# Sheet_2.net
KiCad netlist of a schematic drawn in EasyEDA
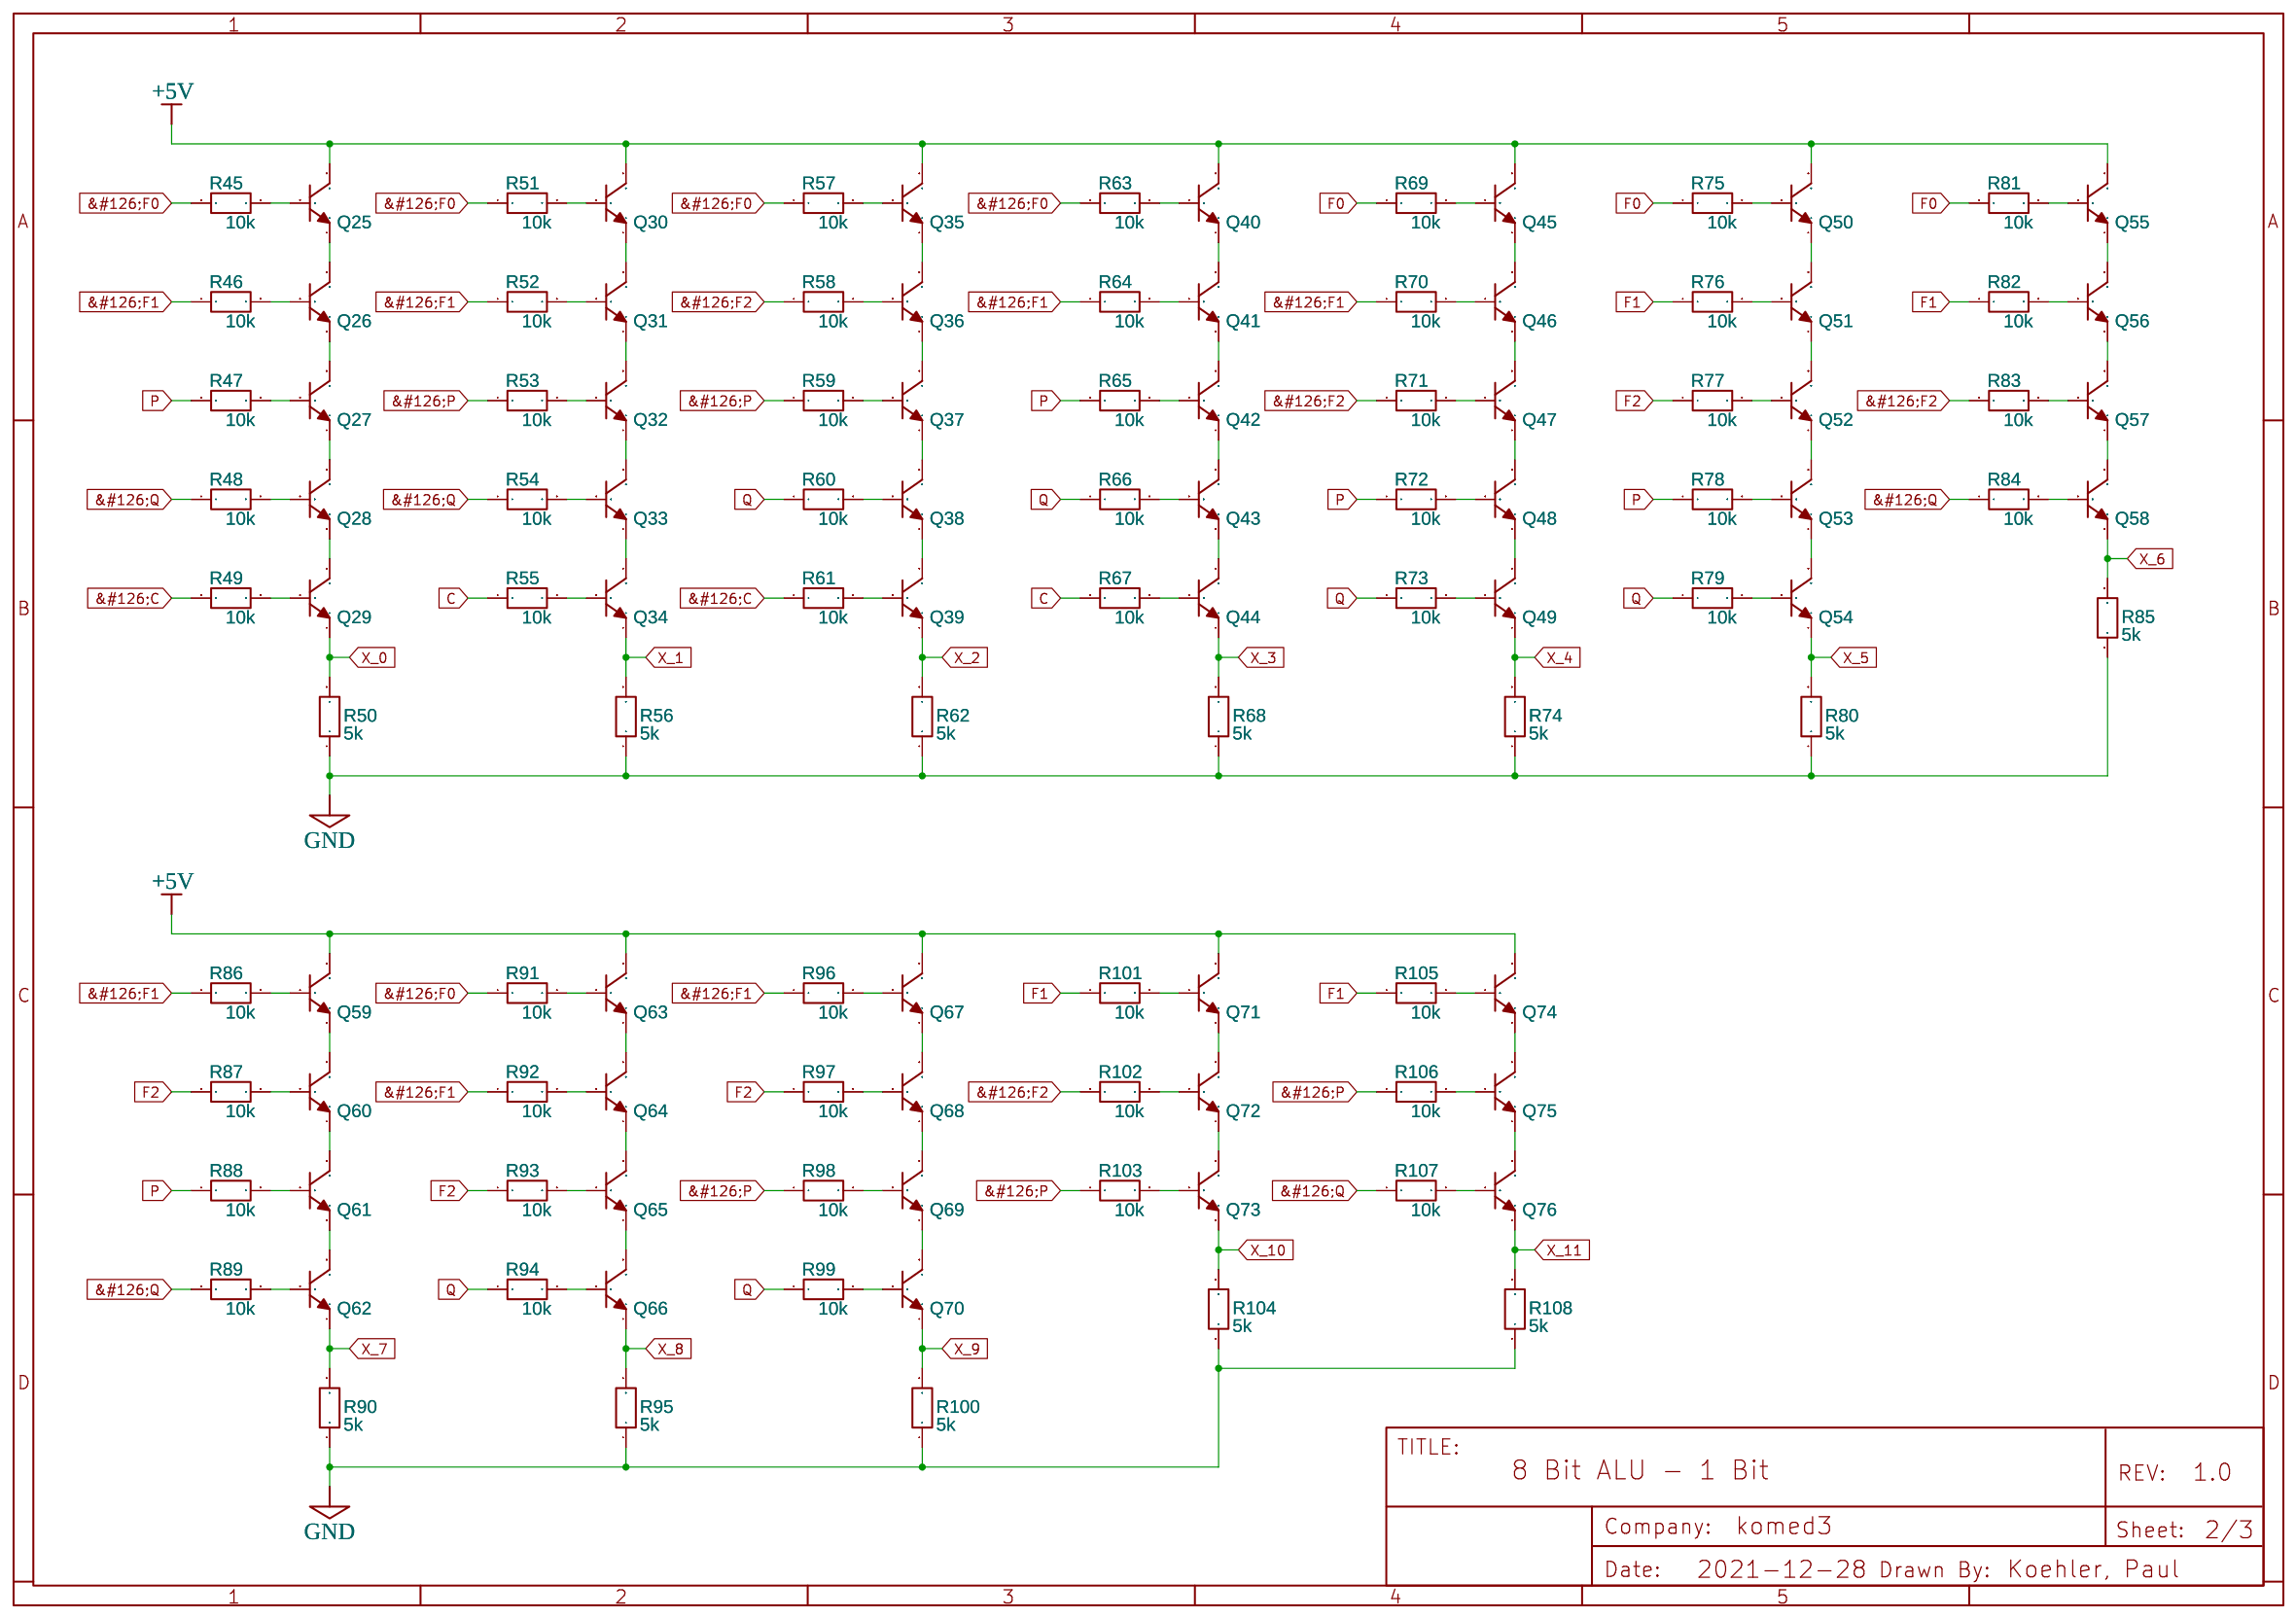
[diagram p0: schematic sheet]

(export (version "E")
  (design (tool "Eeschema 10.0.6"))
  (components
    (comp (ref "Q25")
      (value "2N3904(TO-92)")
      (fields (field (name "BOM_Manufacturer Part") "2N3904") (field (name "BOM_Supplier Part") "C118538"))
      (libsource (lib "") (part "2N3904(TO-92)"))
    )
    (comp (ref "Q26")
      (value "2N3904(TO-92)")
      (fields (field (name "BOM_Manufacturer Part") "2N3904") (field (name "BOM_Supplier Part") "C118538"))
      (libsource (lib "") (part "2N3904(TO-92)"))
    )
    (comp (ref "Q27")
      (value "2N3904(TO-92)")
      (fields (field (name "BOM_Manufacturer Part") "2N3904") (field (name "BOM_Supplier Part") "C118538"))
      (libsource (lib "") (part "2N3904(TO-92)"))
    )
    (comp (ref "Q28")
      (value "2N3904(TO-92)")
      (fields (field (name "BOM_Manufacturer Part") "2N3904") (field (name "BOM_Supplier Part") "C118538"))
      (libsource (lib "") (part "2N3904(TO-92)"))
    )
    (comp (ref "Q29")
      (value "2N3904(TO-92)")
      (fields (field (name "BOM_Manufacturer Part") "2N3904") (field (name "BOM_Supplier Part") "C118538"))
      (libsource (lib "") (part "2N3904(TO-92)"))
    )
    (comp (ref "Q30")
      (value "2N3904(TO-92)")
      (fields (field (name "BOM_Manufacturer Part") "2N3904") (field (name "BOM_Supplier Part") "C118538"))
      (libsource (lib "") (part "2N3904(TO-92)"))
    )
    (comp (ref "Q31")
      (value "2N3904(TO-92)")
      (fields (field (name "BOM_Manufacturer Part") "2N3904") (field (name "BOM_Supplier Part") "C118538"))
      (libsource (lib "") (part "2N3904(TO-92)"))
    )
    (comp (ref "Q32")
      (value "2N3904(TO-92)")
      (fields (field (name "BOM_Manufacturer Part") "2N3904") (field (name "BOM_Supplier Part") "C118538"))
      (libsource (lib "") (part "2N3904(TO-92)"))
    )
    (comp (ref "Q33")
      (value "2N3904(TO-92)")
      (fields (field (name "BOM_Manufacturer Part") "2N3904") (field (name "BOM_Supplier Part") "C118538"))
      (libsource (lib "") (part "2N3904(TO-92)"))
    )
    (comp (ref "Q34")
      (value "2N3904(TO-92)")
      (fields (field (name "BOM_Manufacturer Part") "2N3904") (field (name "BOM_Supplier Part") "C118538"))
      (libsource (lib "") (part "2N3904(TO-92)"))
    )
    (comp (ref "Q35")
      (value "2N3904(TO-92)")
      (fields (field (name "BOM_Manufacturer Part") "2N3904") (field (name "BOM_Supplier Part") "C118538"))
      (libsource (lib "") (part "2N3904(TO-92)"))
    )
    (comp (ref "Q36")
      (value "2N3904(TO-92)")
      (fields (field (name "BOM_Manufacturer Part") "2N3904") (field (name "BOM_Supplier Part") "C118538"))
      (libsource (lib "") (part "2N3904(TO-92)"))
    )
    (comp (ref "Q37")
      (value "2N3904(TO-92)")
      (fields (field (name "BOM_Manufacturer Part") "2N3904") (field (name "BOM_Supplier Part") "C118538"))
      (libsource (lib "") (part "2N3904(TO-92)"))
    )
    (comp (ref "Q38")
      (value "2N3904(TO-92)")
      (fields (field (name "BOM_Manufacturer Part") "2N3904") (field (name "BOM_Supplier Part") "C118538"))
      (libsource (lib "") (part "2N3904(TO-92)"))
    )
    (comp (ref "Q39")
      (value "2N3904(TO-92)")
      (fields (field (name "BOM_Manufacturer Part") "2N3904") (field (name "BOM_Supplier Part") "C118538"))
      (libsource (lib "") (part "2N3904(TO-92)"))
    )
    (comp (ref "Q40")
      (value "2N3904(TO-92)")
      (fields (field (name "BOM_Manufacturer Part") "2N3904") (field (name "BOM_Supplier Part") "C118538"))
      (libsource (lib "") (part "2N3904(TO-92)"))
    )
    (comp (ref "Q41")
      (value "2N3904(TO-92)")
      (fields (field (name "BOM_Manufacturer Part") "2N3904") (field (name "BOM_Supplier Part") "C118538"))
      (libsource (lib "") (part "2N3904(TO-92)"))
    )
    (comp (ref "Q42")
      (value "2N3904(TO-92)")
      (fields (field (name "BOM_Manufacturer Part") "2N3904") (field (name "BOM_Supplier Part") "C118538"))
      (libsource (lib "") (part "2N3904(TO-92)"))
    )
    (comp (ref "Q43")
      (value "2N3904(TO-92)")
      (fields (field (name "BOM_Manufacturer Part") "2N3904") (field (name "BOM_Supplier Part") "C118538"))
      (libsource (lib "") (part "2N3904(TO-92)"))
    )
    (comp (ref "Q44")
      (value "2N3904(TO-92)")
      (fields (field (name "BOM_Manufacturer Part") "2N3904") (field (name "BOM_Supplier Part") "C118538"))
      (libsource (lib "") (part "2N3904(TO-92)"))
    )
    (comp (ref "Q45")
      (value "2N3904(TO-92)")
      (fields (field (name "BOM_Manufacturer Part") "2N3904") (field (name "BOM_Supplier Part") "C118538"))
      (libsource (lib "") (part "2N3904(TO-92)"))
    )
    (comp (ref "Q46")
      (value "2N3904(TO-92)")
      (fields (field (name "BOM_Manufacturer Part") "2N3904") (field (name "BOM_Supplier Part") "C118538"))
      (libsource (lib "") (part "2N3904(TO-92)"))
    )
    (comp (ref "Q47")
      (value "2N3904(TO-92)")
      (fields (field (name "BOM_Manufacturer Part") "2N3904") (field (name "BOM_Supplier Part") "C118538"))
      (libsource (lib "") (part "2N3904(TO-92)"))
    )
    (comp (ref "Q48")
      (value "2N3904(TO-92)")
      (fields (field (name "BOM_Manufacturer Part") "2N3904") (field (name "BOM_Supplier Part") "C118538"))
      (libsource (lib "") (part "2N3904(TO-92)"))
    )
    (comp (ref "Q49")
      (value "2N3904(TO-92)")
      (fields (field (name "BOM_Manufacturer Part") "2N3904") (field (name "BOM_Supplier Part") "C118538"))
      (libsource (lib "") (part "2N3904(TO-92)"))
    )
    (comp (ref "Q50")
      (value "2N3904(TO-92)")
      (fields (field (name "BOM_Manufacturer Part") "2N3904") (field (name "BOM_Supplier Part") "C118538"))
      (libsource (lib "") (part "2N3904(TO-92)"))
    )
    (comp (ref "Q51")
      (value "2N3904(TO-92)")
      (fields (field (name "BOM_Manufacturer Part") "2N3904") (field (name "BOM_Supplier Part") "C118538"))
      (libsource (lib "") (part "2N3904(TO-92)"))
    )
    (comp (ref "Q52")
      (value "2N3904(TO-92)")
      (fields (field (name "BOM_Manufacturer Part") "2N3904") (field (name "BOM_Supplier Part") "C118538"))
      (libsource (lib "") (part "2N3904(TO-92)"))
    )
    (comp (ref "Q53")
      (value "2N3904(TO-92)")
      (fields (field (name "BOM_Manufacturer Part") "2N3904") (field (name "BOM_Supplier Part") "C118538"))
      (libsource (lib "") (part "2N3904(TO-92)"))
    )
    (comp (ref "Q54")
      (value "2N3904(TO-92)")
      (fields (field (name "BOM_Manufacturer Part") "2N3904") (field (name "BOM_Supplier Part") "C118538"))
      (libsource (lib "") (part "2N3904(TO-92)"))
    )
    (comp (ref "Q55")
      (value "2N3904(TO-92)")
      (fields (field (name "BOM_Manufacturer Part") "2N3904") (field (name "BOM_Supplier Part") "C118538"))
      (libsource (lib "") (part "2N3904(TO-92)"))
    )
    (comp (ref "Q56")
      (value "2N3904(TO-92)")
      (fields (field (name "BOM_Manufacturer Part") "2N3904") (field (name "BOM_Supplier Part") "C118538"))
      (libsource (lib "") (part "2N3904(TO-92)"))
    )
    (comp (ref "Q57")
      (value "2N3904(TO-92)")
      (fields (field (name "BOM_Manufacturer Part") "2N3904") (field (name "BOM_Supplier Part") "C118538"))
      (libsource (lib "") (part "2N3904(TO-92)"))
    )
    (comp (ref "Q58")
      (value "2N3904(TO-92)")
      (fields (field (name "BOM_Manufacturer Part") "2N3904") (field (name "BOM_Supplier Part") "C118538"))
      (libsource (lib "") (part "2N3904(TO-92)"))
    )
    (comp (ref "Q59")
      (value "2N3904(TO-92)")
      (fields (field (name "BOM_Manufacturer Part") "2N3904") (field (name "BOM_Supplier Part") "C118538"))
      (libsource (lib "") (part "2N3904(TO-92)"))
    )
    (comp (ref "Q60")
      (value "2N3904(TO-92)")
      (fields (field (name "BOM_Manufacturer Part") "2N3904") (field (name "BOM_Supplier Part") "C118538"))
      (libsource (lib "") (part "2N3904(TO-92)"))
    )
    (comp (ref "Q61")
      (value "2N3904(TO-92)")
      (fields (field (name "BOM_Manufacturer Part") "2N3904") (field (name "BOM_Supplier Part") "C118538"))
      (libsource (lib "") (part "2N3904(TO-92)"))
    )
    (comp (ref "Q62")
      (value "2N3904(TO-92)")
      (fields (field (name "BOM_Manufacturer Part") "2N3904") (field (name "BOM_Supplier Part") "C118538"))
      (libsource (lib "") (part "2N3904(TO-92)"))
    )
    (comp (ref "Q63")
      (value "2N3904(TO-92)")
      (fields (field (name "BOM_Manufacturer Part") "2N3904") (field (name "BOM_Supplier Part") "C118538"))
      (libsource (lib "") (part "2N3904(TO-92)"))
    )
    (comp (ref "Q64")
      (value "2N3904(TO-92)")
      (fields (field (name "BOM_Manufacturer Part") "2N3904") (field (name "BOM_Supplier Part") "C118538"))
      (libsource (lib "") (part "2N3904(TO-92)"))
    )
    (comp (ref "Q65")
      (value "2N3904(TO-92)")
      (fields (field (name "BOM_Manufacturer Part") "2N3904") (field (name "BOM_Supplier Part") "C118538"))
      (libsource (lib "") (part "2N3904(TO-92)"))
    )
    (comp (ref "Q66")
      (value "2N3904(TO-92)")
      (fields (field (name "BOM_Manufacturer Part") "2N3904") (field (name "BOM_Supplier Part") "C118538"))
      (libsource (lib "") (part "2N3904(TO-92)"))
    )
    (comp (ref "Q67")
      (value "2N3904(TO-92)")
      (fields (field (name "BOM_Manufacturer Part") "2N3904") (field (name "BOM_Supplier Part") "C118538"))
      (libsource (lib "") (part "2N3904(TO-92)"))
    )
    (comp (ref "Q68")
      (value "2N3904(TO-92)")
      (fields (field (name "BOM_Manufacturer Part") "2N3904") (field (name "BOM_Supplier Part") "C118538"))
      (libsource (lib "") (part "2N3904(TO-92)"))
    )
    (comp (ref "Q69")
      (value "2N3904(TO-92)")
      (fields (field (name "BOM_Manufacturer Part") "2N3904") (field (name "BOM_Supplier Part") "C118538"))
      (libsource (lib "") (part "2N3904(TO-92)"))
    )
    (comp (ref "Q70")
      (value "2N3904(TO-92)")
      (fields (field (name "BOM_Manufacturer Part") "2N3904") (field (name "BOM_Supplier Part") "C118538"))
      (libsource (lib "") (part "2N3904(TO-92)"))
    )
    (comp (ref "Q71")
      (value "2N3904(TO-92)")
      (fields (field (name "BOM_Manufacturer Part") "2N3904") (field (name "BOM_Supplier Part") "C118538"))
      (libsource (lib "") (part "2N3904(TO-92)"))
    )
    (comp (ref "Q72")
      (value "2N3904(TO-92)")
      (fields (field (name "BOM_Manufacturer Part") "2N3904") (field (name "BOM_Supplier Part") "C118538"))
      (libsource (lib "") (part "2N3904(TO-92)"))
    )
    (comp (ref "Q73")
      (value "2N3904(TO-92)")
      (fields (field (name "BOM_Manufacturer Part") "2N3904") (field (name "BOM_Supplier Part") "C118538"))
      (libsource (lib "") (part "2N3904(TO-92)"))
    )
    (comp (ref "Q74")
      (value "2N3904(TO-92)")
      (fields (field (name "BOM_Manufacturer Part") "2N3904") (field (name "BOM_Supplier Part") "C118538"))
      (libsource (lib "") (part "2N3904(TO-92)"))
    )
    (comp (ref "Q75")
      (value "2N3904(TO-92)")
      (fields (field (name "BOM_Manufacturer Part") "2N3904") (field (name "BOM_Supplier Part") "C118538"))
      (libsource (lib "") (part "2N3904(TO-92)"))
    )
    (comp (ref "Q76")
      (value "2N3904(TO-92)")
      (fields (field (name "BOM_Manufacturer Part") "2N3904") (field (name "BOM_Supplier Part") "C118538"))
      (libsource (lib "") (part "2N3904(TO-92)"))
    )
    (comp (ref "R45") (value "10k") (libsource (lib "") (part "R_AXIAL-0.3_EU_1")))
    (comp (ref "R46") (value "10k") (libsource (lib "") (part "R_AXIAL-0.3_EU_1")))
    (comp (ref "R47") (value "10k") (libsource (lib "") (part "R_AXIAL-0.3_EU_1")))
    (comp (ref "R48") (value "10k") (libsource (lib "") (part "R_AXIAL-0.3_EU_1")))
    (comp (ref "R49") (value "10k") (libsource (lib "") (part "R_AXIAL-0.3_EU_1")))
    (comp (ref "R50") (value "5k") (libsource (lib "") (part "R_AXIAL-0.3_EU")))
    (comp (ref "R51") (value "10k") (libsource (lib "") (part "R_AXIAL-0.3_EU_1")))
    (comp (ref "R52") (value "10k") (libsource (lib "") (part "R_AXIAL-0.3_EU_1")))
    (comp (ref "R53") (value "10k") (libsource (lib "") (part "R_AXIAL-0.3_EU_1")))
    (comp (ref "R54") (value "10k") (libsource (lib "") (part "R_AXIAL-0.3_EU_1")))
    (comp (ref "R55") (value "10k") (libsource (lib "") (part "R_AXIAL-0.3_EU_1")))
    (comp (ref "R56") (value "5k") (libsource (lib "") (part "R_AXIAL-0.3_EU")))
    (comp (ref "R57") (value "10k") (libsource (lib "") (part "R_AXIAL-0.3_EU_1")))
    (comp (ref "R58") (value "10k") (libsource (lib "") (part "R_AXIAL-0.3_EU_1")))
    (comp (ref "R59") (value "10k") (libsource (lib "") (part "R_AXIAL-0.3_EU_1")))
    (comp (ref "R60") (value "10k") (libsource (lib "") (part "R_AXIAL-0.3_EU_1")))
    (comp (ref "R61") (value "10k") (libsource (lib "") (part "R_AXIAL-0.3_EU_1")))
    (comp (ref "R62") (value "5k") (libsource (lib "") (part "R_AXIAL-0.3_EU")))
    (comp (ref "R63") (value "10k") (libsource (lib "") (part "R_AXIAL-0.3_EU_1")))
    (comp (ref "R64") (value "10k") (libsource (lib "") (part "R_AXIAL-0.3_EU_1")))
    (comp (ref "R65") (value "10k") (libsource (lib "") (part "R_AXIAL-0.3_EU_1")))
    (comp (ref "R66") (value "10k") (libsource (lib "") (part "R_AXIAL-0.3_EU_1")))
    (comp (ref "R67") (value "10k") (libsource (lib "") (part "R_AXIAL-0.3_EU_1")))
    (comp (ref "R68") (value "5k") (libsource (lib "") (part "R_AXIAL-0.3_EU")))
    (comp (ref "R69") (value "10k") (libsource (lib "") (part "R_AXIAL-0.3_EU_1")))
    (comp (ref "R70") (value "10k") (libsource (lib "") (part "R_AXIAL-0.3_EU_1")))
    (comp (ref "R71") (value "10k") (libsource (lib "") (part "R_AXIAL-0.3_EU_1")))
    (comp (ref "R72") (value "10k") (libsource (lib "") (part "R_AXIAL-0.3_EU_1")))
    (comp (ref "R73") (value "10k") (libsource (lib "") (part "R_AXIAL-0.3_EU_1")))
    (comp (ref "R74") (value "5k") (libsource (lib "") (part "R_AXIAL-0.3_EU")))
    (comp (ref "R75") (value "10k") (libsource (lib "") (part "R_AXIAL-0.3_EU_1")))
    (comp (ref "R76") (value "10k") (libsource (lib "") (part "R_AXIAL-0.3_EU_1")))
    (comp (ref "R77") (value "10k") (libsource (lib "") (part "R_AXIAL-0.3_EU_1")))
    (comp (ref "R78") (value "10k") (libsource (lib "") (part "R_AXIAL-0.3_EU_1")))
    (comp (ref "R79") (value "10k") (libsource (lib "") (part "R_AXIAL-0.3_EU_1")))
    (comp (ref "R80") (value "5k") (libsource (lib "") (part "R_AXIAL-0.3_EU")))
    (comp (ref "R81") (value "10k") (libsource (lib "") (part "R_AXIAL-0.3_EU_1")))
    (comp (ref "R82") (value "10k") (libsource (lib "") (part "R_AXIAL-0.3_EU_1")))
    (comp (ref "R83") (value "10k") (libsource (lib "") (part "R_AXIAL-0.3_EU_1")))
    (comp (ref "R84") (value "10k") (libsource (lib "") (part "R_AXIAL-0.3_EU_1")))
    (comp (ref "R85") (value "5k") (libsource (lib "") (part "R_AXIAL-0.3_EU")))
    (comp (ref "R86") (value "10k") (libsource (lib "") (part "R_AXIAL-0.3_EU_1")))
    (comp (ref "R87") (value "10k") (libsource (lib "") (part "R_AXIAL-0.3_EU_1")))
    (comp (ref "R88") (value "10k") (libsource (lib "") (part "R_AXIAL-0.3_EU_1")))
    (comp (ref "R89") (value "10k") (libsource (lib "") (part "R_AXIAL-0.3_EU_1")))
    (comp (ref "R90") (value "5k") (libsource (lib "") (part "R_AXIAL-0.3_EU")))
    (comp (ref "R91") (value "10k") (libsource (lib "") (part "R_AXIAL-0.3_EU_1")))
    (comp (ref "R92") (value "10k") (libsource (lib "") (part "R_AXIAL-0.3_EU_1")))
    (comp (ref "R93") (value "10k") (libsource (lib "") (part "R_AXIAL-0.3_EU_1")))
    (comp (ref "R94") (value "10k") (libsource (lib "") (part "R_AXIAL-0.3_EU_1")))
    (comp (ref "R95") (value "5k") (libsource (lib "") (part "R_AXIAL-0.3_EU")))
    (comp (ref "R96") (value "10k") (libsource (lib "") (part "R_AXIAL-0.3_EU_1")))
    (comp (ref "R97") (value "10k") (libsource (lib "") (part "R_AXIAL-0.3_EU_1")))
    (comp (ref "R98") (value "10k") (libsource (lib "") (part "R_AXIAL-0.3_EU_1")))
    (comp (ref "R99") (value "10k") (libsource (lib "") (part "R_AXIAL-0.3_EU_1")))
    (comp (ref "R100") (value "5k") (libsource (lib "") (part "R_AXIAL-0.3_EU")))
    (comp (ref "R101") (value "10k") (libsource (lib "") (part "R_AXIAL-0.3_EU_1")))
    (comp (ref "R102") (value "10k") (libsource (lib "") (part "R_AXIAL-0.3_EU_1")))
    (comp (ref "R103") (value "10k") (libsource (lib "") (part "R_AXIAL-0.3_EU_1")))
    (comp (ref "R104") (value "5k") (libsource (lib "") (part "R_AXIAL-0.3_EU")))
    (comp (ref "R105") (value "10k") (libsource (lib "") (part "R_AXIAL-0.3_EU_1")))
    (comp (ref "R106") (value "10k") (libsource (lib "") (part "R_AXIAL-0.3_EU_1")))
    (comp (ref "R107") (value "10k") (libsource (lib "") (part "R_AXIAL-0.3_EU_1")))
    (comp (ref "R108") (value "5k") (libsource (lib "") (part "R_AXIAL-0.3_EU")))
  )
  (nets
    (net (code "1") (name "&#126;C") (class "Default")
      (node (ref "R49") (pin "1") (pinfunction "1_1") (pintype "unspecified"))
      (node (ref "R61") (pin "1") (pinfunction "1_1") (pintype "unspecified"))
    )
    (net (code "2") (name "&#126;F0") (class "Default")
      (node (ref "R45") (pin "1") (pinfunction "1_1") (pintype "unspecified"))
      (node (ref "R51") (pin "1") (pinfunction "1_1") (pintype "unspecified"))
      (node (ref "R57") (pin "1") (pinfunction "1_1") (pintype "unspecified"))
      (node (ref "R63") (pin "1") (pinfunction "1_1") (pintype "unspecified"))
      (node (ref "R91") (pin "1") (pinfunction "1_1") (pintype "unspecified"))
    )
    (net (code "3") (name "&#126;F1") (class "Default")
      (node (ref "R46") (pin "1") (pinfunction "1_1") (pintype "unspecified"))
      (node (ref "R52") (pin "1") (pinfunction "1_1") (pintype "unspecified"))
      (node (ref "R64") (pin "1") (pinfunction "1_1") (pintype "unspecified"))
      (node (ref "R70") (pin "1") (pinfunction "1_1") (pintype "unspecified"))
      (node (ref "R86") (pin "1") (pinfunction "1_1") (pintype "unspecified"))
      (node (ref "R92") (pin "1") (pinfunction "1_1") (pintype "unspecified"))
      (node (ref "R96") (pin "1") (pinfunction "1_1") (pintype "unspecified"))
    )
    (net (code "4") (name "&#126;F2") (class "Default")
      (node (ref "R102") (pin "1") (pinfunction "1_1") (pintype "unspecified"))
      (node (ref "R58") (pin "1") (pinfunction "1_1") (pintype "unspecified"))
      (node (ref "R71") (pin "1") (pinfunction "1_1") (pintype "unspecified"))
      (node (ref "R83") (pin "1") (pinfunction "1_1") (pintype "unspecified"))
    )
    (net (code "5") (name "&#126;P") (class "Default")
      (node (ref "R103") (pin "1") (pinfunction "1_1") (pintype "unspecified"))
      (node (ref "R106") (pin "1") (pinfunction "1_1") (pintype "unspecified"))
      (node (ref "R53") (pin "1") (pinfunction "1_1") (pintype "unspecified"))
      (node (ref "R59") (pin "1") (pinfunction "1_1") (pintype "unspecified"))
      (node (ref "R98") (pin "1") (pinfunction "1_1") (pintype "unspecified"))
    )
    (net (code "6") (name "&#126;Q") (class "Default")
      (node (ref "R107") (pin "1") (pinfunction "1_1") (pintype "unspecified"))
      (node (ref "R48") (pin "1") (pinfunction "1_1") (pintype "unspecified"))
      (node (ref "R54") (pin "1") (pinfunction "1_1") (pintype "unspecified"))
      (node (ref "R84") (pin "1") (pinfunction "1_1") (pintype "unspecified"))
      (node (ref "R89") (pin "1") (pinfunction "1_1") (pintype "unspecified"))
    )
    (net (code "7") (name "+5V") (class "Default")
      (node (ref "Q25") (pin "3") (pinfunction "C_3") (pintype "unspecified"))
      (node (ref "Q30") (pin "3") (pinfunction "C_3") (pintype "unspecified"))
      (node (ref "Q35") (pin "3") (pinfunction "C_3") (pintype "unspecified"))
      (node (ref "Q40") (pin "3") (pinfunction "C_3") (pintype "unspecified"))
      (node (ref "Q45") (pin "3") (pinfunction "C_3") (pintype "unspecified"))
      (node (ref "Q50") (pin "3") (pinfunction "C_3") (pintype "unspecified"))
      (node (ref "Q55") (pin "3") (pinfunction "C_3") (pintype "unspecified"))
      (node (ref "Q59") (pin "3") (pinfunction "C_3") (pintype "unspecified"))
      (node (ref "Q63") (pin "3") (pinfunction "C_3") (pintype "unspecified"))
      (node (ref "Q67") (pin "3") (pinfunction "C_3") (pintype "unspecified"))
      (node (ref "Q71") (pin "3") (pinfunction "C_3") (pintype "unspecified"))
      (node (ref "Q74") (pin "3") (pinfunction "C_3") (pintype "unspecified"))
    )
    (net (code "8") (name "C") (class "Default")
      (node (ref "R55") (pin "1") (pinfunction "1_1") (pintype "unspecified"))
      (node (ref "R67") (pin "1") (pinfunction "1_1") (pintype "unspecified"))
    )
    (net (code "9") (name "F0") (class "Default")
      (node (ref "R69") (pin "1") (pinfunction "1_1") (pintype "unspecified"))
      (node (ref "R75") (pin "1") (pinfunction "1_1") (pintype "unspecified"))
      (node (ref "R81") (pin "1") (pinfunction "1_1") (pintype "unspecified"))
    )
    (net (code "10") (name "F1") (class "Default")
      (node (ref "R101") (pin "1") (pinfunction "1_1") (pintype "unspecified"))
      (node (ref "R105") (pin "1") (pinfunction "1_1") (pintype "unspecified"))
      (node (ref "R76") (pin "1") (pinfunction "1_1") (pintype "unspecified"))
      (node (ref "R82") (pin "1") (pinfunction "1_1") (pintype "unspecified"))
    )
    (net (code "11") (name "F2") (class "Default")
      (node (ref "R77") (pin "1") (pinfunction "1_1") (pintype "unspecified"))
      (node (ref "R87") (pin "1") (pinfunction "1_1") (pintype "unspecified"))
      (node (ref "R93") (pin "1") (pinfunction "1_1") (pintype "unspecified"))
      (node (ref "R97") (pin "1") (pinfunction "1_1") (pintype "unspecified"))
    )
    (net (code "12") (name "GND") (class "Default")
      (node (ref "R100") (pin "1") (pinfunction "1_1") (pintype "unspecified"))
      (node (ref "R104") (pin "1") (pinfunction "1_1") (pintype "unspecified"))
      (node (ref "R108") (pin "1") (pinfunction "1_1") (pintype "unspecified"))
      (node (ref "R50") (pin "1") (pinfunction "1_1") (pintype "unspecified"))
      (node (ref "R56") (pin "1") (pinfunction "1_1") (pintype "unspecified"))
      (node (ref "R62") (pin "1") (pinfunction "1_1") (pintype "unspecified"))
      (node (ref "R68") (pin "1") (pinfunction "1_1") (pintype "unspecified"))
      (node (ref "R74") (pin "1") (pinfunction "1_1") (pintype "unspecified"))
      (node (ref "R80") (pin "1") (pinfunction "1_1") (pintype "unspecified"))
      (node (ref "R85") (pin "1") (pinfunction "1_1") (pintype "unspecified"))
      (node (ref "R90") (pin "1") (pinfunction "1_1") (pintype "unspecified"))
      (node (ref "R95") (pin "1") (pinfunction "1_1") (pintype "unspecified"))
    )
    (net (code "13") (name "Net-(Q25-B)") (class "Default")
      (node (ref "Q25") (pin "2") (pinfunction "B_2") (pintype "unspecified"))
      (node (ref "R45") (pin "2") (pinfunction "2_2") (pintype "unspecified"))
    )
    (net (code "14") (name "Net-(Q25-E)") (class "Default")
      (node (ref "Q25") (pin "1") (pinfunction "E_1") (pintype "unspecified"))
      (node (ref "Q26") (pin "3") (pinfunction "C_3") (pintype "unspecified"))
    )
    (net (code "15") (name "Net-(Q26-B)") (class "Default")
      (node (ref "Q26") (pin "2") (pinfunction "B_2") (pintype "unspecified"))
      (node (ref "R46") (pin "2") (pinfunction "2_2") (pintype "unspecified"))
    )
    (net (code "16") (name "Net-(Q26-E)") (class "Default")
      (node (ref "Q26") (pin "1") (pinfunction "E_1") (pintype "unspecified"))
      (node (ref "Q27") (pin "3") (pinfunction "C_3") (pintype "unspecified"))
    )
    (net (code "17") (name "Net-(Q27-B)") (class "Default")
      (node (ref "Q27") (pin "2") (pinfunction "B_2") (pintype "unspecified"))
      (node (ref "R47") (pin "2") (pinfunction "2_2") (pintype "unspecified"))
    )
    (net (code "18") (name "Net-(Q27-E)") (class "Default")
      (node (ref "Q27") (pin "1") (pinfunction "E_1") (pintype "unspecified"))
      (node (ref "Q28") (pin "3") (pinfunction "C_3") (pintype "unspecified"))
    )
    (net (code "19") (name "Net-(Q28-B)") (class "Default")
      (node (ref "Q28") (pin "2") (pinfunction "B_2") (pintype "unspecified"))
      (node (ref "R48") (pin "2") (pinfunction "2_2") (pintype "unspecified"))
    )
    (net (code "20") (name "Net-(Q28-E)") (class "Default")
      (node (ref "Q28") (pin "1") (pinfunction "E_1") (pintype "unspecified"))
      (node (ref "Q29") (pin "3") (pinfunction "C_3") (pintype "unspecified"))
    )
    (net (code "21") (name "Net-(Q29-B)") (class "Default")
      (node (ref "Q29") (pin "2") (pinfunction "B_2") (pintype "unspecified"))
      (node (ref "R49") (pin "2") (pinfunction "2_2") (pintype "unspecified"))
    )
    (net (code "22") (name "Net-(Q30-B)") (class "Default")
      (node (ref "Q30") (pin "2") (pinfunction "B_2") (pintype "unspecified"))
      (node (ref "R51") (pin "2") (pinfunction "2_2") (pintype "unspecified"))
    )
    (net (code "23") (name "Net-(Q30-E)") (class "Default")
      (node (ref "Q30") (pin "1") (pinfunction "E_1") (pintype "unspecified"))
      (node (ref "Q31") (pin "3") (pinfunction "C_3") (pintype "unspecified"))
    )
    (net (code "24") (name "Net-(Q31-B)") (class "Default")
      (node (ref "Q31") (pin "2") (pinfunction "B_2") (pintype "unspecified"))
      (node (ref "R52") (pin "2") (pinfunction "2_2") (pintype "unspecified"))
    )
    (net (code "25") (name "Net-(Q31-E)") (class "Default")
      (node (ref "Q31") (pin "1") (pinfunction "E_1") (pintype "unspecified"))
      (node (ref "Q32") (pin "3") (pinfunction "C_3") (pintype "unspecified"))
    )
    (net (code "26") (name "Net-(Q32-B)") (class "Default")
      (node (ref "Q32") (pin "2") (pinfunction "B_2") (pintype "unspecified"))
      (node (ref "R53") (pin "2") (pinfunction "2_2") (pintype "unspecified"))
    )
    (net (code "27") (name "Net-(Q32-E)") (class "Default")
      (node (ref "Q32") (pin "1") (pinfunction "E_1") (pintype "unspecified"))
      (node (ref "Q33") (pin "3") (pinfunction "C_3") (pintype "unspecified"))
    )
    (net (code "28") (name "Net-(Q33-B)") (class "Default")
      (node (ref "Q33") (pin "2") (pinfunction "B_2") (pintype "unspecified"))
      (node (ref "R54") (pin "2") (pinfunction "2_2") (pintype "unspecified"))
    )
    (net (code "29") (name "Net-(Q33-E)") (class "Default")
      (node (ref "Q33") (pin "1") (pinfunction "E_1") (pintype "unspecified"))
      (node (ref "Q34") (pin "3") (pinfunction "C_3") (pintype "unspecified"))
    )
    (net (code "30") (name "Net-(Q34-B)") (class "Default")
      (node (ref "Q34") (pin "2") (pinfunction "B_2") (pintype "unspecified"))
      (node (ref "R55") (pin "2") (pinfunction "2_2") (pintype "unspecified"))
    )
    (net (code "31") (name "Net-(Q35-B)") (class "Default")
      (node (ref "Q35") (pin "2") (pinfunction "B_2") (pintype "unspecified"))
      (node (ref "R57") (pin "2") (pinfunction "2_2") (pintype "unspecified"))
    )
    (net (code "32") (name "Net-(Q35-E)") (class "Default")
      (node (ref "Q35") (pin "1") (pinfunction "E_1") (pintype "unspecified"))
      (node (ref "Q36") (pin "3") (pinfunction "C_3") (pintype "unspecified"))
    )
    (net (code "33") (name "Net-(Q36-B)") (class "Default")
      (node (ref "Q36") (pin "2") (pinfunction "B_2") (pintype "unspecified"))
      (node (ref "R58") (pin "2") (pinfunction "2_2") (pintype "unspecified"))
    )
    (net (code "34") (name "Net-(Q36-E)") (class "Default")
      (node (ref "Q36") (pin "1") (pinfunction "E_1") (pintype "unspecified"))
      (node (ref "Q37") (pin "3") (pinfunction "C_3") (pintype "unspecified"))
    )
    (net (code "35") (name "Net-(Q37-B)") (class "Default")
      (node (ref "Q37") (pin "2") (pinfunction "B_2") (pintype "unspecified"))
      (node (ref "R59") (pin "2") (pinfunction "2_2") (pintype "unspecified"))
    )
    (net (code "36") (name "Net-(Q37-E)") (class "Default")
      (node (ref "Q37") (pin "1") (pinfunction "E_1") (pintype "unspecified"))
      (node (ref "Q38") (pin "3") (pinfunction "C_3") (pintype "unspecified"))
    )
    (net (code "37") (name "Net-(Q38-B)") (class "Default")
      (node (ref "Q38") (pin "2") (pinfunction "B_2") (pintype "unspecified"))
      (node (ref "R60") (pin "2") (pinfunction "2_2") (pintype "unspecified"))
    )
    (net (code "38") (name "Net-(Q38-E)") (class "Default")
      (node (ref "Q38") (pin "1") (pinfunction "E_1") (pintype "unspecified"))
      (node (ref "Q39") (pin "3") (pinfunction "C_3") (pintype "unspecified"))
    )
    (net (code "39") (name "Net-(Q39-B)") (class "Default")
      (node (ref "Q39") (pin "2") (pinfunction "B_2") (pintype "unspecified"))
      (node (ref "R61") (pin "2") (pinfunction "2_2") (pintype "unspecified"))
    )
    (net (code "40") (name "Net-(Q40-B)") (class "Default")
      (node (ref "Q40") (pin "2") (pinfunction "B_2") (pintype "unspecified"))
      (node (ref "R63") (pin "2") (pinfunction "2_2") (pintype "unspecified"))
    )
    (net (code "41") (name "Net-(Q40-E)") (class "Default")
      (node (ref "Q40") (pin "1") (pinfunction "E_1") (pintype "unspecified"))
      (node (ref "Q41") (pin "3") (pinfunction "C_3") (pintype "unspecified"))
    )
    (net (code "42") (name "Net-(Q41-B)") (class "Default")
      (node (ref "Q41") (pin "2") (pinfunction "B_2") (pintype "unspecified"))
      (node (ref "R64") (pin "2") (pinfunction "2_2") (pintype "unspecified"))
    )
    (net (code "43") (name "Net-(Q41-E)") (class "Default")
      (node (ref "Q41") (pin "1") (pinfunction "E_1") (pintype "unspecified"))
      (node (ref "Q42") (pin "3") (pinfunction "C_3") (pintype "unspecified"))
    )
    (net (code "44") (name "Net-(Q42-B)") (class "Default")
      (node (ref "Q42") (pin "2") (pinfunction "B_2") (pintype "unspecified"))
      (node (ref "R65") (pin "2") (pinfunction "2_2") (pintype "unspecified"))
    )
    (net (code "45") (name "Net-(Q42-E)") (class "Default")
      (node (ref "Q42") (pin "1") (pinfunction "E_1") (pintype "unspecified"))
      (node (ref "Q43") (pin "3") (pinfunction "C_3") (pintype "unspecified"))
    )
    (net (code "46") (name "Net-(Q43-B)") (class "Default")
      (node (ref "Q43") (pin "2") (pinfunction "B_2") (pintype "unspecified"))
      (node (ref "R66") (pin "2") (pinfunction "2_2") (pintype "unspecified"))
    )
    (net (code "47") (name "Net-(Q43-E)") (class "Default")
      (node (ref "Q43") (pin "1") (pinfunction "E_1") (pintype "unspecified"))
      (node (ref "Q44") (pin "3") (pinfunction "C_3") (pintype "unspecified"))
    )
    (net (code "48") (name "Net-(Q44-B)") (class "Default")
      (node (ref "Q44") (pin "2") (pinfunction "B_2") (pintype "unspecified"))
      (node (ref "R67") (pin "2") (pinfunction "2_2") (pintype "unspecified"))
    )
    (net (code "49") (name "Net-(Q45-B)") (class "Default")
      (node (ref "Q45") (pin "2") (pinfunction "B_2") (pintype "unspecified"))
      (node (ref "R69") (pin "2") (pinfunction "2_2") (pintype "unspecified"))
    )
    (net (code "50") (name "Net-(Q45-E)") (class "Default")
      (node (ref "Q45") (pin "1") (pinfunction "E_1") (pintype "unspecified"))
      (node (ref "Q46") (pin "3") (pinfunction "C_3") (pintype "unspecified"))
    )
    (net (code "51") (name "Net-(Q46-B)") (class "Default")
      (node (ref "Q46") (pin "2") (pinfunction "B_2") (pintype "unspecified"))
      (node (ref "R70") (pin "2") (pinfunction "2_2") (pintype "unspecified"))
    )
    (net (code "52") (name "Net-(Q46-E)") (class "Default")
      (node (ref "Q46") (pin "1") (pinfunction "E_1") (pintype "unspecified"))
      (node (ref "Q47") (pin "3") (pinfunction "C_3") (pintype "unspecified"))
    )
    (net (code "53") (name "Net-(Q47-B)") (class "Default")
      (node (ref "Q47") (pin "2") (pinfunction "B_2") (pintype "unspecified"))
      (node (ref "R71") (pin "2") (pinfunction "2_2") (pintype "unspecified"))
    )
    (net (code "54") (name "Net-(Q47-E)") (class "Default")
      (node (ref "Q47") (pin "1") (pinfunction "E_1") (pintype "unspecified"))
      (node (ref "Q48") (pin "3") (pinfunction "C_3") (pintype "unspecified"))
    )
    (net (code "55") (name "Net-(Q48-B)") (class "Default")
      (node (ref "Q48") (pin "2") (pinfunction "B_2") (pintype "unspecified"))
      (node (ref "R72") (pin "2") (pinfunction "2_2") (pintype "unspecified"))
    )
    (net (code "56") (name "Net-(Q48-E)") (class "Default")
      (node (ref "Q48") (pin "1") (pinfunction "E_1") (pintype "unspecified"))
      (node (ref "Q49") (pin "3") (pinfunction "C_3") (pintype "unspecified"))
    )
    (net (code "57") (name "Net-(Q49-B)") (class "Default")
      (node (ref "Q49") (pin "2") (pinfunction "B_2") (pintype "unspecified"))
      (node (ref "R73") (pin "2") (pinfunction "2_2") (pintype "unspecified"))
    )
    (net (code "58") (name "Net-(Q50-B)") (class "Default")
      (node (ref "Q50") (pin "2") (pinfunction "B_2") (pintype "unspecified"))
      (node (ref "R75") (pin "2") (pinfunction "2_2") (pintype "unspecified"))
    )
    (net (code "59") (name "Net-(Q50-E)") (class "Default")
      (node (ref "Q50") (pin "1") (pinfunction "E_1") (pintype "unspecified"))
      (node (ref "Q51") (pin "3") (pinfunction "C_3") (pintype "unspecified"))
    )
    (net (code "60") (name "Net-(Q51-B)") (class "Default")
      (node (ref "Q51") (pin "2") (pinfunction "B_2") (pintype "unspecified"))
      (node (ref "R76") (pin "2") (pinfunction "2_2") (pintype "unspecified"))
    )
    (net (code "61") (name "Net-(Q51-E)") (class "Default")
      (node (ref "Q51") (pin "1") (pinfunction "E_1") (pintype "unspecified"))
      (node (ref "Q52") (pin "3") (pinfunction "C_3") (pintype "unspecified"))
    )
    (net (code "62") (name "Net-(Q52-B)") (class "Default")
      (node (ref "Q52") (pin "2") (pinfunction "B_2") (pintype "unspecified"))
      (node (ref "R77") (pin "2") (pinfunction "2_2") (pintype "unspecified"))
    )
    (net (code "63") (name "Net-(Q52-E)") (class "Default")
      (node (ref "Q52") (pin "1") (pinfunction "E_1") (pintype "unspecified"))
      (node (ref "Q53") (pin "3") (pinfunction "C_3") (pintype "unspecified"))
    )
    (net (code "64") (name "Net-(Q53-B)") (class "Default")
      (node (ref "Q53") (pin "2") (pinfunction "B_2") (pintype "unspecified"))
      (node (ref "R78") (pin "2") (pinfunction "2_2") (pintype "unspecified"))
    )
    (net (code "65") (name "Net-(Q53-E)") (class "Default")
      (node (ref "Q53") (pin "1") (pinfunction "E_1") (pintype "unspecified"))
      (node (ref "Q54") (pin "3") (pinfunction "C_3") (pintype "unspecified"))
    )
    (net (code "66") (name "Net-(Q54-B)") (class "Default")
      (node (ref "Q54") (pin "2") (pinfunction "B_2") (pintype "unspecified"))
      (node (ref "R79") (pin "2") (pinfunction "2_2") (pintype "unspecified"))
    )
    (net (code "67") (name "Net-(Q55-B)") (class "Default")
      (node (ref "Q55") (pin "2") (pinfunction "B_2") (pintype "unspecified"))
      (node (ref "R81") (pin "2") (pinfunction "2_2") (pintype "unspecified"))
    )
    (net (code "68") (name "Net-(Q55-E)") (class "Default")
      (node (ref "Q55") (pin "1") (pinfunction "E_1") (pintype "unspecified"))
      (node (ref "Q56") (pin "3") (pinfunction "C_3") (pintype "unspecified"))
    )
    (net (code "69") (name "Net-(Q56-B)") (class "Default")
      (node (ref "Q56") (pin "2") (pinfunction "B_2") (pintype "unspecified"))
      (node (ref "R82") (pin "2") (pinfunction "2_2") (pintype "unspecified"))
    )
    (net (code "70") (name "Net-(Q56-E)") (class "Default")
      (node (ref "Q56") (pin "1") (pinfunction "E_1") (pintype "unspecified"))
      (node (ref "Q57") (pin "3") (pinfunction "C_3") (pintype "unspecified"))
    )
    (net (code "71") (name "Net-(Q57-B)") (class "Default")
      (node (ref "Q57") (pin "2") (pinfunction "B_2") (pintype "unspecified"))
      (node (ref "R83") (pin "2") (pinfunction "2_2") (pintype "unspecified"))
    )
    (net (code "72") (name "Net-(Q57-E)") (class "Default")
      (node (ref "Q57") (pin "1") (pinfunction "E_1") (pintype "unspecified"))
      (node (ref "Q58") (pin "3") (pinfunction "C_3") (pintype "unspecified"))
    )
    (net (code "73") (name "Net-(Q58-B)") (class "Default")
      (node (ref "Q58") (pin "2") (pinfunction "B_2") (pintype "unspecified"))
      (node (ref "R84") (pin "2") (pinfunction "2_2") (pintype "unspecified"))
    )
    (net (code "74") (name "Net-(Q59-B)") (class "Default")
      (node (ref "Q59") (pin "2") (pinfunction "B_2") (pintype "unspecified"))
      (node (ref "R86") (pin "2") (pinfunction "2_2") (pintype "unspecified"))
    )
    (net (code "75") (name "Net-(Q59-E)") (class "Default")
      (node (ref "Q59") (pin "1") (pinfunction "E_1") (pintype "unspecified"))
      (node (ref "Q60") (pin "3") (pinfunction "C_3") (pintype "unspecified"))
    )
    (net (code "76") (name "Net-(Q60-B)") (class "Default")
      (node (ref "Q60") (pin "2") (pinfunction "B_2") (pintype "unspecified"))
      (node (ref "R87") (pin "2") (pinfunction "2_2") (pintype "unspecified"))
    )
    (net (code "77") (name "Net-(Q60-E)") (class "Default")
      (node (ref "Q60") (pin "1") (pinfunction "E_1") (pintype "unspecified"))
      (node (ref "Q61") (pin "3") (pinfunction "C_3") (pintype "unspecified"))
    )
    (net (code "78") (name "Net-(Q61-B)") (class "Default")
      (node (ref "Q61") (pin "2") (pinfunction "B_2") (pintype "unspecified"))
      (node (ref "R88") (pin "2") (pinfunction "2_2") (pintype "unspecified"))
    )
    (net (code "79") (name "Net-(Q61-E)") (class "Default")
      (node (ref "Q61") (pin "1") (pinfunction "E_1") (pintype "unspecified"))
      (node (ref "Q62") (pin "3") (pinfunction "C_3") (pintype "unspecified"))
    )
    (net (code "80") (name "Net-(Q62-B)") (class "Default")
      (node (ref "Q62") (pin "2") (pinfunction "B_2") (pintype "unspecified"))
      (node (ref "R89") (pin "2") (pinfunction "2_2") (pintype "unspecified"))
    )
    (net (code "81") (name "Net-(Q63-B)") (class "Default")
      (node (ref "Q63") (pin "2") (pinfunction "B_2") (pintype "unspecified"))
      (node (ref "R91") (pin "2") (pinfunction "2_2") (pintype "unspecified"))
    )
    (net (code "82") (name "Net-(Q63-E)") (class "Default")
      (node (ref "Q63") (pin "1") (pinfunction "E_1") (pintype "unspecified"))
      (node (ref "Q64") (pin "3") (pinfunction "C_3") (pintype "unspecified"))
    )
    (net (code "83") (name "Net-(Q64-B)") (class "Default")
      (node (ref "Q64") (pin "2") (pinfunction "B_2") (pintype "unspecified"))
      (node (ref "R92") (pin "2") (pinfunction "2_2") (pintype "unspecified"))
    )
    (net (code "84") (name "Net-(Q64-E)") (class "Default")
      (node (ref "Q64") (pin "1") (pinfunction "E_1") (pintype "unspecified"))
      (node (ref "Q65") (pin "3") (pinfunction "C_3") (pintype "unspecified"))
    )
    (net (code "85") (name "Net-(Q65-B)") (class "Default")
      (node (ref "Q65") (pin "2") (pinfunction "B_2") (pintype "unspecified"))
      (node (ref "R93") (pin "2") (pinfunction "2_2") (pintype "unspecified"))
    )
    (net (code "86") (name "Net-(Q65-E)") (class "Default")
      (node (ref "Q65") (pin "1") (pinfunction "E_1") (pintype "unspecified"))
      (node (ref "Q66") (pin "3") (pinfunction "C_3") (pintype "unspecified"))
    )
    (net (code "87") (name "Net-(Q66-B)") (class "Default")
      (node (ref "Q66") (pin "2") (pinfunction "B_2") (pintype "unspecified"))
      (node (ref "R94") (pin "2") (pinfunction "2_2") (pintype "unspecified"))
    )
    (net (code "88") (name "Net-(Q67-B)") (class "Default")
      (node (ref "Q67") (pin "2") (pinfunction "B_2") (pintype "unspecified"))
      (node (ref "R96") (pin "2") (pinfunction "2_2") (pintype "unspecified"))
    )
    (net (code "89") (name "Net-(Q67-E)") (class "Default")
      (node (ref "Q67") (pin "1") (pinfunction "E_1") (pintype "unspecified"))
      (node (ref "Q68") (pin "3") (pinfunction "C_3") (pintype "unspecified"))
    )
    (net (code "90") (name "Net-(Q68-B)") (class "Default")
      (node (ref "Q68") (pin "2") (pinfunction "B_2") (pintype "unspecified"))
      (node (ref "R97") (pin "2") (pinfunction "2_2") (pintype "unspecified"))
    )
    (net (code "91") (name "Net-(Q68-E)") (class "Default")
      (node (ref "Q68") (pin "1") (pinfunction "E_1") (pintype "unspecified"))
      (node (ref "Q69") (pin "3") (pinfunction "C_3") (pintype "unspecified"))
    )
    (net (code "92") (name "Net-(Q69-B)") (class "Default")
      (node (ref "Q69") (pin "2") (pinfunction "B_2") (pintype "unspecified"))
      (node (ref "R98") (pin "2") (pinfunction "2_2") (pintype "unspecified"))
    )
    (net (code "93") (name "Net-(Q69-E)") (class "Default")
      (node (ref "Q69") (pin "1") (pinfunction "E_1") (pintype "unspecified"))
      (node (ref "Q70") (pin "3") (pinfunction "C_3") (pintype "unspecified"))
    )
    (net (code "94") (name "Net-(Q70-B)") (class "Default")
      (node (ref "Q70") (pin "2") (pinfunction "B_2") (pintype "unspecified"))
      (node (ref "R99") (pin "2") (pinfunction "2_2") (pintype "unspecified"))
    )
    (net (code "95") (name "Net-(Q71-B)") (class "Default")
      (node (ref "Q71") (pin "2") (pinfunction "B_2") (pintype "unspecified"))
      (node (ref "R101") (pin "2") (pinfunction "2_2") (pintype "unspecified"))
    )
    (net (code "96") (name "Net-(Q71-E)") (class "Default")
      (node (ref "Q71") (pin "1") (pinfunction "E_1") (pintype "unspecified"))
      (node (ref "Q72") (pin "3") (pinfunction "C_3") (pintype "unspecified"))
    )
    (net (code "97") (name "Net-(Q72-B)") (class "Default")
      (node (ref "Q72") (pin "2") (pinfunction "B_2") (pintype "unspecified"))
      (node (ref "R102") (pin "2") (pinfunction "2_2") (pintype "unspecified"))
    )
    (net (code "98") (name "Net-(Q72-E)") (class "Default")
      (node (ref "Q72") (pin "1") (pinfunction "E_1") (pintype "unspecified"))
      (node (ref "Q73") (pin "3") (pinfunction "C_3") (pintype "unspecified"))
    )
    (net (code "99") (name "Net-(Q73-B)") (class "Default")
      (node (ref "Q73") (pin "2") (pinfunction "B_2") (pintype "unspecified"))
      (node (ref "R103") (pin "2") (pinfunction "2_2") (pintype "unspecified"))
    )
    (net (code "100") (name "Net-(Q74-B)") (class "Default")
      (node (ref "Q74") (pin "2") (pinfunction "B_2") (pintype "unspecified"))
      (node (ref "R105") (pin "2") (pinfunction "2_2") (pintype "unspecified"))
    )
    (net (code "101") (name "Net-(Q74-E)") (class "Default")
      (node (ref "Q74") (pin "1") (pinfunction "E_1") (pintype "unspecified"))
      (node (ref "Q75") (pin "3") (pinfunction "C_3") (pintype "unspecified"))
    )
    (net (code "102") (name "Net-(Q75-B)") (class "Default")
      (node (ref "Q75") (pin "2") (pinfunction "B_2") (pintype "unspecified"))
      (node (ref "R106") (pin "2") (pinfunction "2_2") (pintype "unspecified"))
    )
    (net (code "103") (name "Net-(Q75-E)") (class "Default")
      (node (ref "Q75") (pin "1") (pinfunction "E_1") (pintype "unspecified"))
      (node (ref "Q76") (pin "3") (pinfunction "C_3") (pintype "unspecified"))
    )
    (net (code "104") (name "Net-(Q76-B)") (class "Default")
      (node (ref "Q76") (pin "2") (pinfunction "B_2") (pintype "unspecified"))
      (node (ref "R107") (pin "2") (pinfunction "2_2") (pintype "unspecified"))
    )
    (net (code "105") (name "P") (class "Default")
      (node (ref "R47") (pin "1") (pinfunction "1_1") (pintype "unspecified"))
      (node (ref "R65") (pin "1") (pinfunction "1_1") (pintype "unspecified"))
      (node (ref "R72") (pin "1") (pinfunction "1_1") (pintype "unspecified"))
      (node (ref "R78") (pin "1") (pinfunction "1_1") (pintype "unspecified"))
      (node (ref "R88") (pin "1") (pinfunction "1_1") (pintype "unspecified"))
    )
    (net (code "106") (name "Q") (class "Default")
      (node (ref "R60") (pin "1") (pinfunction "1_1") (pintype "unspecified"))
      (node (ref "R66") (pin "1") (pinfunction "1_1") (pintype "unspecified"))
      (node (ref "R73") (pin "1") (pinfunction "1_1") (pintype "unspecified"))
      (node (ref "R79") (pin "1") (pinfunction "1_1") (pintype "unspecified"))
      (node (ref "R94") (pin "1") (pinfunction "1_1") (pintype "unspecified"))
      (node (ref "R99") (pin "1") (pinfunction "1_1") (pintype "unspecified"))
    )
    (net (code "107") (name "X_0") (class "Default")
      (node (ref "Q29") (pin "1") (pinfunction "E_1") (pintype "unspecified"))
      (node (ref "R50") (pin "2") (pinfunction "2_2") (pintype "unspecified"))
    )
    (net (code "108") (name "X_1") (class "Default")
      (node (ref "Q34") (pin "1") (pinfunction "E_1") (pintype "unspecified"))
      (node (ref "R56") (pin "2") (pinfunction "2_2") (pintype "unspecified"))
    )
    (net (code "109") (name "X_2") (class "Default")
      (node (ref "Q39") (pin "1") (pinfunction "E_1") (pintype "unspecified"))
      (node (ref "R62") (pin "2") (pinfunction "2_2") (pintype "unspecified"))
    )
    (net (code "110") (name "X_3") (class "Default")
      (node (ref "Q44") (pin "1") (pinfunction "E_1") (pintype "unspecified"))
      (node (ref "R68") (pin "2") (pinfunction "2_2") (pintype "unspecified"))
    )
    (net (code "111") (name "X_4") (class "Default")
      (node (ref "Q49") (pin "1") (pinfunction "E_1") (pintype "unspecified"))
      (node (ref "R74") (pin "2") (pinfunction "2_2") (pintype "unspecified"))
    )
    (net (code "112") (name "X_5") (class "Default")
      (node (ref "Q54") (pin "1") (pinfunction "E_1") (pintype "unspecified"))
      (node (ref "R80") (pin "2") (pinfunction "2_2") (pintype "unspecified"))
    )
    (net (code "113") (name "X_6") (class "Default")
      (node (ref "Q58") (pin "1") (pinfunction "E_1") (pintype "unspecified"))
      (node (ref "R85") (pin "2") (pinfunction "2_2") (pintype "unspecified"))
    )
    (net (code "114") (name "X_7") (class "Default")
      (node (ref "Q62") (pin "1") (pinfunction "E_1") (pintype "unspecified"))
      (node (ref "R90") (pin "2") (pinfunction "2_2") (pintype "unspecified"))
    )
    (net (code "115") (name "X_8") (class "Default")
      (node (ref "Q66") (pin "1") (pinfunction "E_1") (pintype "unspecified"))
      (node (ref "R95") (pin "2") (pinfunction "2_2") (pintype "unspecified"))
    )
    (net (code "116") (name "X_9") (class "Default")
      (node (ref "Q70") (pin "1") (pinfunction "E_1") (pintype "unspecified"))
      (node (ref "R100") (pin "2") (pinfunction "2_2") (pintype "unspecified"))
    )
    (net (code "117") (name "X_10") (class "Default")
      (node (ref "Q73") (pin "1") (pinfunction "E_1") (pintype "unspecified"))
      (node (ref "R104") (pin "2") (pinfunction "2_2") (pintype "unspecified"))
    )
    (net (code "118") (name "X_11") (class "Default")
      (node (ref "Q76") (pin "1") (pinfunction "E_1") (pintype "unspecified"))
      (node (ref "R108") (pin "2") (pinfunction "2_2") (pintype "unspecified"))
    )
  )
)
